# Haar.net
KiCad netlist of a schematic drawn in EAGLE
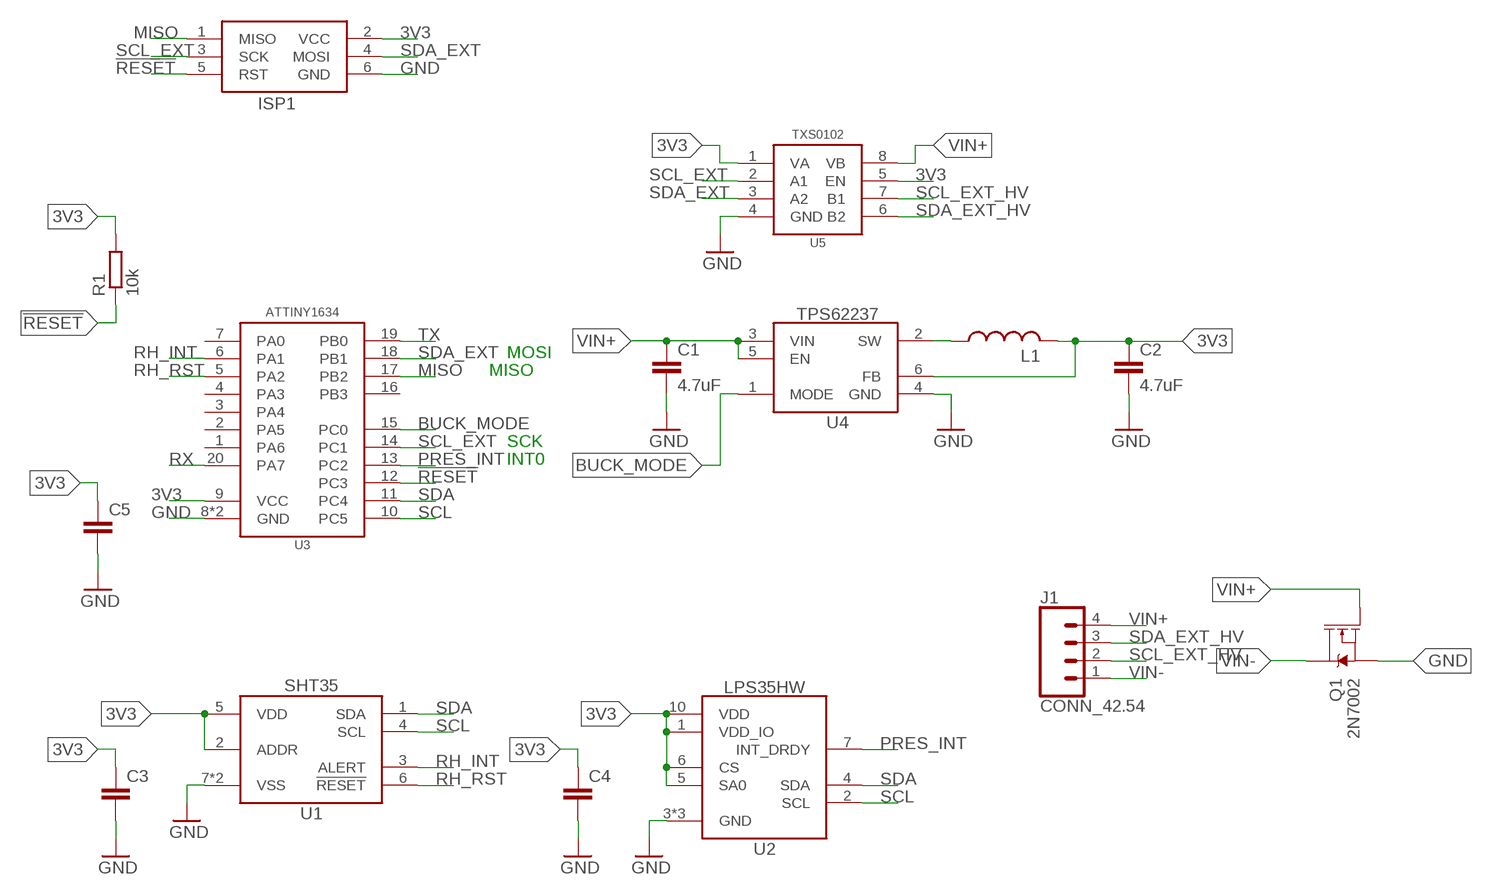
[diagram p0: schematic, sheet 1]

(export (version "E")
  (design (tool "Eeschema 10.0.6"))
  (components
    (comp (ref "C1")
      (value "4.7uF")
      (footprint "eagle-import:C0402")
      (libsource (lib "eagle-import") (part "C-EUC0402"))
    )
    (comp (ref "C2")
      (value "4.7uF")
      (footprint "eagle-import:C0402")
      (libsource (lib "eagle-import") (part "C-EUC0402"))
    )
    (comp (ref "C3")
      (value "C-EU0.1UFC0402")
      (footprint "eagle-import:C0402")
      (fields (field (name "MF") "Murata") (field (name "MPN") "GCM155R71C104KA55D"))
      (libsource (lib "eagle-import") (part "C-EUC04020.1UF"))
    )
    (comp (ref "C4")
      (value "C-EU0.1UFC0402")
      (footprint "eagle-import:C0402")
      (fields (field (name "MF") "Murata") (field (name "MPN") "GCM155R71C104KA55D"))
      (libsource (lib "eagle-import") (part "C-EUC04020.1UF"))
    )
    (comp (ref "C5")
      (value "C-EU0.1UFC0402")
      (footprint "eagle-import:C0402")
      (fields (field (name "MF") "Murata") (field (name "MPN") "GCM155R71C104KA55D"))
      (libsource (lib "eagle-import") (part "C-EUC04020.1UF"))
    )
    (comp (ref "ISP1")
      (value "AVRISP1.27MM")
      (footprint "eagle-import:2X3_1.27")
      (libsource (lib "eagle-import") (part "AVRISP1.27MM"))
    )
    (comp (ref "J1")
      (value "CONN_42.54")
      (footprint "eagle-import:1X04")
      (libsource (lib "eagle-import") (part "CONN_42.54"))
    )
    (comp (ref "L1")
      (value "INDUCTOR0805")
      (footprint "eagle-import:0805")
      (libsource (lib "eagle-import") (part "INDUCTOR0805"))
    )
    (comp (ref "Q1")
      (value "2N7002")
      (footprint "eagle-import:SOT323")
      (fields (field (name "MF") "Diodes Incorporated") (field (name "MPN") "2N7002W-7-F"))
      (libsource (lib "eagle-import") (part "MOSFET-NCH-2N7002PW"))
    )
    (comp (ref "R1")
      (value "10k")
      (footprint "eagle-import:R0402")
      (fields (field (name "MF") "Yageo") (field (name "MPN") "RC0402JR-0710KL"))
      (libsource (lib "eagle-import") (part "R-EU_R040210K"))
    )
    (comp (ref "U1")
      (value "SHT35DFN")
      (footprint "eagle-import:DFN_8_2.5X2.5")
      (fields
        (field (name "DISP") "SHT35")
        (field (name "MF") "Sensirion")
        (field (name "MPN") "SHT35-DIS-F2.5KS")
      )
      (libsource (lib "eagle-import") (part "SHT3DFN5"))
    )
    (comp (ref "U2")
      (value "LPS35HW")
      (footprint "eagle-import:CCLGA10L")
      (fields (field (name "DISP") "LPS35HW") (field (name "MF") "ST") (field (name "MPN") "LPS35HWTR"))
      (libsource (lib "eagle-import") (part "LPS3HW5"))
    )
    (comp (ref "U3")
      (value "ATTINY1634QFN")
      (footprint "eagle-import:QFN20")
      (fields (field (name "MF") "Atmel") (field (name "MPN") "ATTINY1634-MUR"))
      (libsource (lib "eagle-import") (part "ATTINY1634QFN"))
    )
    (comp (ref "U4")
      (value "TPS62237DRY")
      (footprint "eagle-import:DRY0006A")
      (fields (field (name "DISP") "TPS62237") (field (name "MF") "TI") (field (name "MPN") "TPS62237DRYR"))
      (libsource (lib "eagle-import") (part "TPS6223DRY7"))
    )
    (comp (ref "U5")
      (value "TXS0102DQM")
      (footprint "eagle-import:DQM_R-PX2SON-N8")
      (fields (field (name "MF") "TI") (field (name "MPN") "TXS0102DQMR"))
      (libsource (lib "eagle-import") (part "TXS0102DQM"))
    )
  )
  (nets
    (net (code "1") (name "/MISO") (class "Default")
      (node (ref "ISP1") (pin "1") (pinfunction "MISO_1") (pintype "input"))
      (node (ref "U3") (pin "17") (pinfunction "PB2_17") (pintype "bidirectional"))
    )
    (net (code "2") (name "/PRES_INT") (class "Default")
      (node (ref "U2") (pin "7") (pinfunction "INT_DRDY_7") (pintype "output"))
      (node (ref "U3") (pin "13") (pinfunction "PC2_13") (pintype "bidirectional"))
    )
    (net (code "3") (name "/RH_INT") (class "Default")
      (node (ref "U1") (pin "3") (pinfunction "ALERT_3") (pintype "output"))
      (node (ref "U3") (pin "6") (pinfunction "PA1_6") (pintype "bidirectional"))
    )
    (net (code "4") (name "/RH_RST") (class "Default")
      (node (ref "U1") (pin "6") (pinfunction "~{RESET}_6") (pintype "input"))
      (node (ref "U3") (pin "5") (pinfunction "PA2_5") (pintype "bidirectional"))
    )
    (net (code "5") (name "/RX") (class "Default")
      (node (ref "U3") (pin "20") (pinfunction "PA7_20") (pintype "bidirectional"))
    )
    (net (code "6") (name "/SCL") (class "Default")
      (node (ref "U1") (pin "4") (pinfunction "SCL_4") (pintype "input"))
      (node (ref "U2") (pin "2") (pinfunction "SCL_2") (pintype "input"))
      (node (ref "U3") (pin "10") (pinfunction "PC5_10") (pintype "bidirectional"))
    )
    (net (code "7") (name "/SCL_EXT") (class "Default")
      (node (ref "ISP1") (pin "3") (pinfunction "SCK_3") (pintype "output"))
      (node (ref "U3") (pin "14") (pinfunction "PC1_14") (pintype "bidirectional"))
      (node (ref "U5") (pin "2") (pinfunction "A1_2") (pintype "bidirectional"))
    )
    (net (code "8") (name "/SCL_EXT_HV") (class "Default")
      (node (ref "J1") (pin "2") (pinfunction "2_2") (pintype "passive"))
      (node (ref "U5") (pin "7") (pinfunction "B1_7") (pintype "bidirectional"))
    )
    (net (code "9") (name "/SDA") (class "Default")
      (node (ref "U1") (pin "1") (pinfunction "SDA_1") (pintype "bidirectional"))
      (node (ref "U2") (pin "4") (pinfunction "SDA_4") (pintype "bidirectional"))
      (node (ref "U3") (pin "11") (pinfunction "PC4_11") (pintype "bidirectional"))
    )
    (net (code "10") (name "/SDA_EXT") (class "Default")
      (node (ref "ISP1") (pin "4") (pinfunction "MOSI_4") (pintype "output"))
      (node (ref "U3") (pin "18") (pinfunction "PB1_18") (pintype "bidirectional"))
      (node (ref "U5") (pin "3") (pinfunction "A2_3") (pintype "bidirectional"))
    )
    (net (code "11") (name "/SDA_EXT_HV") (class "Default")
      (node (ref "J1") (pin "3") (pinfunction "3_3") (pintype "passive"))
      (node (ref "U5") (pin "6") (pinfunction "B2_6") (pintype "bidirectional"))
    )
    (net (code "12") (name "/TX") (class "Default")
      (node (ref "U3") (pin "19") (pinfunction "PB0_19") (pintype "bidirectional"))
    )
    (net (code "13") (name "/~{RESET}") (class "Default")
      (node (ref "ISP1") (pin "5") (pinfunction "RST_5") (pintype "output"))
      (node (ref "R1") (pin "1") (pinfunction "1_1") (pintype "passive"))
      (node (ref "U3") (pin "12") (pinfunction "PC3_12") (pintype "bidirectional"))
    )
    (net (code "14") (name "3V3") (class "Default")
      (node (ref "C2") (pin "1") (pinfunction "1_1") (pintype "passive"))
      (node (ref "C3") (pin "1") (pinfunction "1_1") (pintype "passive"))
      (node (ref "C4") (pin "1") (pinfunction "1_1") (pintype "passive"))
      (node (ref "C5") (pin "1") (pinfunction "1_1") (pintype "passive"))
      (node (ref "ISP1") (pin "2") (pinfunction "VCC_2") (pintype "power_in"))
      (node (ref "L1") (pin "2") (pinfunction "2_2") (pintype "passive"))
      (node (ref "R1") (pin "2") (pinfunction "2_2") (pintype "passive"))
      (node (ref "U1") (pin "2") (pinfunction "ADDR_2") (pintype "input"))
      (node (ref "U1") (pin "5") (pinfunction "VDD_5") (pintype "power_in"))
      (node (ref "U2") (pin "1") (pinfunction "VDD_IO_1") (pintype "power_in"))
      (node (ref "U2") (pin "10") (pinfunction "VDD_10") (pintype "power_in"))
      (node (ref "U2") (pin "5") (pinfunction "SA0_5") (pintype "input"))
      (node (ref "U2") (pin "6") (pinfunction "CS_6") (pintype "input"))
      (node (ref "U3") (pin "9") (pinfunction "VCC_9") (pintype "power_in"))
      (node (ref "U4") (pin "6") (pinfunction "FB_6") (pintype "input"))
      (node (ref "U5") (pin "1") (pinfunction "VA_1") (pintype "power_in"))
      (node (ref "U5") (pin "5") (pinfunction "EN_5") (pintype "input"))
    )
    (net (code "15") (name "BUCK_MODE") (class "Default")
      (node (ref "U3") (pin "15") (pinfunction "PC0_15") (pintype "bidirectional"))
      (node (ref "U4") (pin "1") (pinfunction "MODE_1") (pintype "input"))
    )
    (net (code "16") (name "GND") (class "Default")
      (node (ref "C1") (pin "2") (pinfunction "2_2") (pintype "passive"))
      (node (ref "C2") (pin "2") (pinfunction "2_2") (pintype "passive"))
      (node (ref "C3") (pin "2") (pinfunction "2_2") (pintype "passive"))
      (node (ref "C4") (pin "2") (pinfunction "2_2") (pintype "passive"))
      (node (ref "C5") (pin "2") (pinfunction "2_2") (pintype "passive"))
      (node (ref "ISP1") (pin "6") (pinfunction "GND_6") (pintype "power_in"))
      (node (ref "Q1") (pin "2") (pinfunction "S_2") (pintype "bidirectional"))
      (node (ref "U1") (pin "7") (pinfunction "VSS_7") (pintype "power_in"))
      (node (ref "U1") (pin "8") (pinfunction "VSS_8") (pintype "power_in"))
      (node (ref "U2") (pin "3") (pinfunction "GND_3") (pintype "power_in"))
      (node (ref "U2") (pin "8") (pinfunction "GND_8") (pintype "power_in"))
      (node (ref "U2") (pin "9") (pinfunction "GND_9") (pintype "power_in"))
      (node (ref "U3") (pin "8") (pinfunction "GND_8") (pintype "power_in"))
      (node (ref "U3") (pin "EP") (pinfunction "GND_EP") (pintype "power_in"))
      (node (ref "U4") (pin "4") (pinfunction "GND_4") (pintype "power_in"))
      (node (ref "U5") (pin "4") (pinfunction "GND_4") (pintype "power_in"))
    )
    (net (code "17") (name "Net-(U4-SW)") (class "Default")
      (node (ref "L1") (pin "1") (pinfunction "1_1") (pintype "passive"))
      (node (ref "U4") (pin "2") (pinfunction "SW_2") (pintype "output"))
    )
    (net (code "18") (name "VIN+") (class "Default")
      (node (ref "C1") (pin "1") (pinfunction "1_1") (pintype "passive"))
      (node (ref "J1") (pin "4") (pinfunction "4_4") (pintype "passive"))
      (node (ref "Q1") (pin "1") (pinfunction "G_1") (pintype "bidirectional"))
      (node (ref "U4") (pin "3") (pinfunction "VIN_3") (pintype "power_in"))
      (node (ref "U4") (pin "5") (pinfunction "EN_5") (pintype "input"))
      (node (ref "U5") (pin "8") (pinfunction "VB_8") (pintype "power_in"))
    )
    (net (code "19") (name "VIN-") (class "Default")
      (node (ref "J1") (pin "1") (pinfunction "1_1") (pintype "passive"))
      (node (ref "Q1") (pin "3") (pinfunction "D_3") (pintype "bidirectional"))
    )
    (net (code "20") (name "unconnected-(U3-PA0-Pad7)") (class "Default")
      (node (ref "U3") (pin "7") (pinfunction "PA0_7") (pintype "bidirectional"))
    )
    (net (code "21") (name "unconnected-(U3-PA3-Pad4)") (class "Default")
      (node (ref "U3") (pin "4") (pinfunction "PA3_4") (pintype "bidirectional"))
    )
    (net (code "22") (name "unconnected-(U3-PA4-Pad3)") (class "Default")
      (node (ref "U3") (pin "3") (pinfunction "PA4_3") (pintype "bidirectional"))
    )
    (net (code "23") (name "unconnected-(U3-PA5-Pad2)") (class "Default")
      (node (ref "U3") (pin "2") (pinfunction "PA5_2") (pintype "bidirectional"))
    )
    (net (code "24") (name "unconnected-(U3-PA6-Pad1)") (class "Default")
      (node (ref "U3") (pin "1") (pinfunction "PA6_1") (pintype "bidirectional"))
    )
    (net (code "25") (name "unconnected-(U3-PB3-Pad16)") (class "Default")
      (node (ref "U3") (pin "16") (pinfunction "PB3_16") (pintype "bidirectional"))
    )
  )
)
